# MersenneTwister.net
KiCad netlist of a schematic drawn in EAGLE
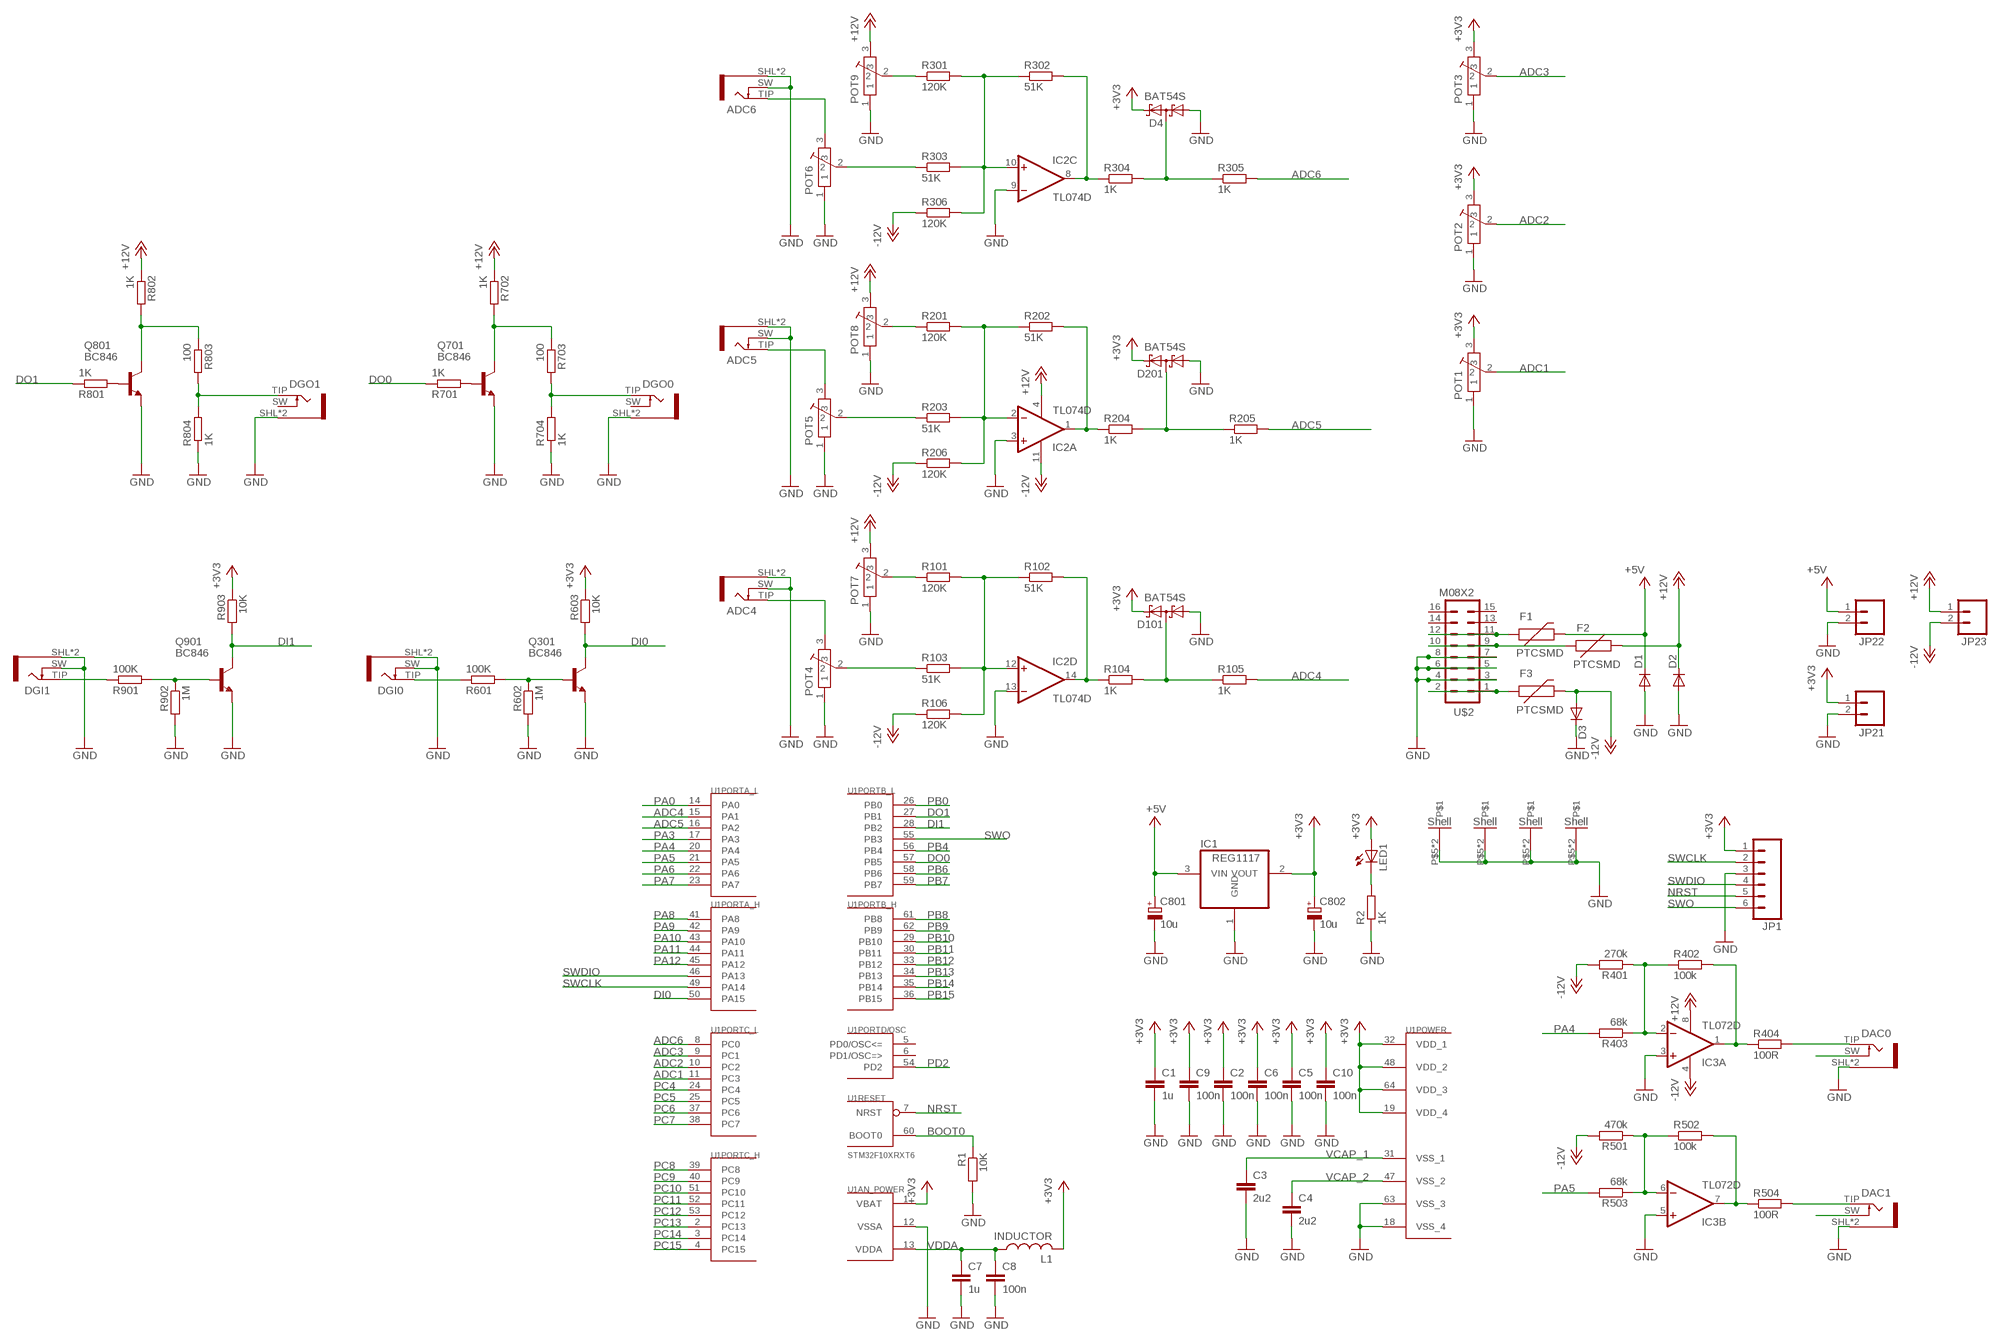
[diagram p0: schematic, sheet 1]

(export (version "E")
  (design (tool "Eeschema 10.0.6"))
  (components
    (comp (ref "ADC4")
      (value "JACK-PJ-301B")
      (footprint "eagle-import:PJ-301B")
      (libsource (lib "eagle-import") (part "JACK-PJ-301B"))
    )
    (comp (ref "ADC5")
      (value "JACK-PJ-301B")
      (footprint "eagle-import:PJ-301B")
      (libsource (lib "eagle-import") (part "JACK-PJ-301B"))
    )
    (comp (ref "ADC6")
      (value "JACK-PJ-301B")
      (footprint "eagle-import:PJ-301B")
      (libsource (lib "eagle-import") (part "JACK-PJ-301B"))
    )
    (comp (ref "C1")
      (value "1u")
      (footprint "eagle-import:C0603")
      (libsource (lib "eagle-import") (part "C-EUC0603"))
    )
    (comp (ref "C2")
      (value "100n")
      (footprint "eagle-import:C0603")
      (libsource (lib "eagle-import") (part "C-EUC0603"))
    )
    (comp (ref "C3")
      (value "2u2")
      (footprint "eagle-import:C0603")
      (libsource (lib "eagle-import") (part "C-EUC0603"))
    )
    (comp (ref "C4")
      (value "2u2")
      (footprint "eagle-import:C0603")
      (libsource (lib "eagle-import") (part "C-EUC0603"))
    )
    (comp (ref "C5")
      (value "100n")
      (footprint "eagle-import:C0603")
      (libsource (lib "eagle-import") (part "C-EUC0603"))
    )
    (comp (ref "C6")
      (value "100n")
      (footprint "eagle-import:C0603")
      (libsource (lib "eagle-import") (part "C-EUC0603"))
    )
    (comp (ref "C7")
      (value "1u")
      (footprint "eagle-import:C0603")
      (libsource (lib "eagle-import") (part "C-EUC0603"))
    )
    (comp (ref "C8")
      (value "100n")
      (footprint "eagle-import:C0603")
      (libsource (lib "eagle-import") (part "C-EUC0603"))
    )
    (comp (ref "C9")
      (value "100n")
      (footprint "eagle-import:C0603")
      (libsource (lib "eagle-import") (part "C-EUC0603"))
    )
    (comp (ref "C10")
      (value "100n")
      (footprint "eagle-import:C0603")
      (libsource (lib "eagle-import") (part "C-EUC0603"))
    )
    (comp (ref "C801")
      (value "10u")
      (footprint "eagle-import:PANASONIC_A")
      (libsource (lib "eagle-import") (part "CPOL-EUA"))
    )
    (comp (ref "C802")
      (value "10u")
      (footprint "eagle-import:PANASONIC_A")
      (libsource (lib "eagle-import") (part "CPOL-EUA"))
    )
    (comp (ref "D1")
      (value "DIODESMA")
      (footprint "eagle-import:SMA-DIODE")
      (libsource (lib "eagle-import") (part "DIODESMA"))
    )
    (comp (ref "D2")
      (value "DIODESMA")
      (footprint "eagle-import:SMA-DIODE")
      (libsource (lib "eagle-import") (part "DIODESMA"))
    )
    (comp (ref "D3")
      (value "DIODESMA")
      (footprint "eagle-import:SMA-DIODE")
      (libsource (lib "eagle-import") (part "DIODESMA"))
    )
    (comp (ref "D4")
      (value "BAT54S")
      (footprint "eagle-import:SOT23")
      (libsource (lib "eagle-import") (part "BAT54S"))
    )
    (comp (ref "D101")
      (value "BAT54S")
      (footprint "eagle-import:SOT23")
      (libsource (lib "eagle-import") (part "BAT54S"))
    )
    (comp (ref "D201")
      (value "BAT54S")
      (footprint "eagle-import:SOT23")
      (libsource (lib "eagle-import") (part "BAT54S"))
    )
    (comp (ref "DAC0")
      (value "JACK-PJ-301B")
      (footprint "eagle-import:PJ-301B")
      (libsource (lib "eagle-import") (part "JACK-PJ-301B"))
    )
    (comp (ref "DAC1")
      (value "JACK-PJ-301B")
      (footprint "eagle-import:PJ-301B")
      (libsource (lib "eagle-import") (part "JACK-PJ-301B"))
    )
    (comp (ref "DGI0")
      (value "JACK-PJ-301B")
      (footprint "eagle-import:PJ-301B")
      (libsource (lib "eagle-import") (part "JACK-PJ-301B"))
    )
    (comp (ref "DGI1")
      (value "JACK-PJ-301B")
      (footprint "eagle-import:PJ-301B")
      (libsource (lib "eagle-import") (part "JACK-PJ-301B"))
    )
    (comp (ref "DGO0")
      (value "JACK-PJ-301B")
      (footprint "eagle-import:PJ-301B")
      (libsource (lib "eagle-import") (part "JACK-PJ-301B"))
    )
    (comp (ref "DGO1")
      (value "JACK-PJ-301B")
      (footprint "eagle-import:PJ-301B")
      (libsource (lib "eagle-import") (part "JACK-PJ-301B"))
    )
    (comp (ref "F1")
      (value "PTCSMD")
      (footprint "eagle-import:PTC-1206")
      (libsource (lib "eagle-import") (part "PTCSMD"))
    )
    (comp (ref "F2")
      (value "PTCSMD")
      (footprint "eagle-import:PTC-1206")
      (libsource (lib "eagle-import") (part "PTCSMD"))
    )
    (comp (ref "F3")
      (value "PTCSMD")
      (footprint "eagle-import:PTC-1206")
      (libsource (lib "eagle-import") (part "PTCSMD"))
    )
    (comp (ref "IC1")
      (value "REG1117")
      (footprint "eagle-import:SOT223")
      (libsource (lib "eagle-import") (part "REG1117"))
    )
    (comp (ref "IC2")
      (value "TL074D")
      (footprint "eagle-import:SO14")
      (libsource (lib "eagle-import") (part "TL074D"))
    )
    (comp (ref "IC3")
      (value "TL072D")
      (footprint "eagle-import:SO08")
      (libsource (lib "eagle-import") (part "TL072D"))
    )
    (comp (ref "JP1")
      (value "M06SIP")
      (footprint "eagle-import:1X06")
      (libsource (lib "eagle-import") (part "M06SIP"))
    )
    (comp (ref "JP21")
      (value "M02PTH")
      (footprint "eagle-import:1X02")
      (libsource (lib "eagle-import") (part "M02PTH"))
    )
    (comp (ref "JP22")
      (value "M02PTH")
      (footprint "eagle-import:1X02")
      (libsource (lib "eagle-import") (part "M02PTH"))
    )
    (comp (ref "JP23")
      (value "M02PTH")
      (footprint "eagle-import:1X02")
      (libsource (lib "eagle-import") (part "M02PTH"))
    )
    (comp (ref "L1")
      (value "INDUCTOR")
      (footprint "eagle-import:0603")
      (libsource (lib "eagle-import") (part "INDUCTOR"))
    )
    (comp (ref "LED1")
      (value "LEDCHIPLED_0603")
      (footprint "eagle-import:CHIPLED_0603")
      (libsource (lib "eagle-import") (part "LEDCHIPLED_0603"))
    )
    (comp (ref "POT1")
      (value "POT-ALPS-RK09L1140")
      (footprint "eagle-import:POT-ALPS-RK09L1140")
      (libsource (lib "eagle-import") (part "POT-ALPS-RK09L1140"))
    )
    (comp (ref "POT2")
      (value "POT-ALPS-RK09L1140")
      (footprint "eagle-import:POT-ALPS-RK09L1140")
      (libsource (lib "eagle-import") (part "POT-ALPS-RK09L1140"))
    )
    (comp (ref "POT3")
      (value "POT-ALPS-RK09L1140")
      (footprint "eagle-import:POT-ALPS-RK09L1140")
      (libsource (lib "eagle-import") (part "POT-ALPS-RK09L1140"))
    )
    (comp (ref "POT4")
      (value "POT-ALPS-RK09L1140")
      (footprint "eagle-import:POT-ALPS-RK09L1140")
      (libsource (lib "eagle-import") (part "POT-ALPS-RK09L1140"))
    )
    (comp (ref "POT5")
      (value "POT-ALPS-RK09L1140")
      (footprint "eagle-import:POT-ALPS-RK09L1140")
      (libsource (lib "eagle-import") (part "POT-ALPS-RK09L1140"))
    )
    (comp (ref "POT6")
      (value "POT-ALPS-RK09L1140")
      (footprint "eagle-import:POT-ALPS-RK09L1140")
      (libsource (lib "eagle-import") (part "POT-ALPS-RK09L1140"))
    )
    (comp (ref "POT7")
      (value "POT-ALPS-RK09L1140")
      (footprint "eagle-import:POT-ALPS-RK09L1140")
      (libsource (lib "eagle-import") (part "POT-ALPS-RK09L1140"))
    )
    (comp (ref "POT8")
      (value "POT-ALPS-RK09L1140")
      (footprint "eagle-import:POT-ALPS-RK09L1140")
      (libsource (lib "eagle-import") (part "POT-ALPS-RK09L1140"))
    )
    (comp (ref "POT9")
      (value "POT-ALPS-RK09L1140")
      (footprint "eagle-import:POT-ALPS-RK09L1140")
      (libsource (lib "eagle-import") (part "POT-ALPS-RK09L1140"))
    )
    (comp (ref "Q301")
      (value "BC846")
      (footprint "eagle-import:SOT23")
      (libsource (lib "eagle-import") (part "BC846"))
    )
    (comp (ref "Q701")
      (value "BC846")
      (footprint "eagle-import:SOT23")
      (libsource (lib "eagle-import") (part "BC846"))
    )
    (comp (ref "Q801")
      (value "BC846")
      (footprint "eagle-import:SOT23")
      (libsource (lib "eagle-import") (part "BC846"))
    )
    (comp (ref "Q901")
      (value "BC846")
      (footprint "eagle-import:SOT23")
      (libsource (lib "eagle-import") (part "BC846"))
    )
    (comp (ref "R1")
      (value "10K")
      (footprint "eagle-import:R0603")
      (libsource (lib "eagle-import") (part "R-EU_R0603"))
    )
    (comp (ref "R2")
      (value "1K")
      (footprint "eagle-import:R0603")
      (libsource (lib "eagle-import") (part "R-EU_R0603"))
    )
    (comp (ref "R101")
      (value "120K")
      (footprint "eagle-import:R0603")
      (libsource (lib "eagle-import") (part "R-EU_R0603"))
    )
    (comp (ref "R102")
      (value "51K")
      (footprint "eagle-import:R0603")
      (libsource (lib "eagle-import") (part "R-EU_R0603"))
    )
    (comp (ref "R103")
      (value "51K")
      (footprint "eagle-import:R0603")
      (libsource (lib "eagle-import") (part "R-EU_R0603"))
    )
    (comp (ref "R104")
      (value "1K")
      (footprint "eagle-import:R0603")
      (libsource (lib "eagle-import") (part "R-EU_R0603"))
    )
    (comp (ref "R105")
      (value "1K")
      (footprint "eagle-import:R0603")
      (libsource (lib "eagle-import") (part "R-EU_R0603"))
    )
    (comp (ref "R106")
      (value "120K")
      (footprint "eagle-import:R0603")
      (libsource (lib "eagle-import") (part "R-EU_R0603"))
    )
    (comp (ref "R201")
      (value "120K")
      (footprint "eagle-import:R0603")
      (libsource (lib "eagle-import") (part "R-EU_R0603"))
    )
    (comp (ref "R202")
      (value "51K")
      (footprint "eagle-import:R0603")
      (libsource (lib "eagle-import") (part "R-EU_R0603"))
    )
    (comp (ref "R203")
      (value "51K")
      (footprint "eagle-import:R0603")
      (libsource (lib "eagle-import") (part "R-EU_R0603"))
    )
    (comp (ref "R204")
      (value "1K")
      (footprint "eagle-import:R0603")
      (libsource (lib "eagle-import") (part "R-EU_R0603"))
    )
    (comp (ref "R205")
      (value "1K")
      (footprint "eagle-import:R0603")
      (libsource (lib "eagle-import") (part "R-EU_R0603"))
    )
    (comp (ref "R206")
      (value "120K")
      (footprint "eagle-import:R0603")
      (libsource (lib "eagle-import") (part "R-EU_R0603"))
    )
    (comp (ref "R301")
      (value "120K")
      (footprint "eagle-import:R0603")
      (libsource (lib "eagle-import") (part "R-EU_R0603"))
    )
    (comp (ref "R302")
      (value "51K")
      (footprint "eagle-import:R0603")
      (libsource (lib "eagle-import") (part "R-EU_R0603"))
    )
    (comp (ref "R303")
      (value "51K")
      (footprint "eagle-import:R0603")
      (libsource (lib "eagle-import") (part "R-EU_R0603"))
    )
    (comp (ref "R304")
      (value "1K")
      (footprint "eagle-import:R0603")
      (libsource (lib "eagle-import") (part "R-EU_R0603"))
    )
    (comp (ref "R305")
      (value "1K")
      (footprint "eagle-import:R0603")
      (libsource (lib "eagle-import") (part "R-EU_R0603"))
    )
    (comp (ref "R306")
      (value "120K")
      (footprint "eagle-import:R0603")
      (libsource (lib "eagle-import") (part "R-EU_R0603"))
    )
    (comp (ref "R401")
      (value "270k")
      (footprint "eagle-import:R0603")
      (libsource (lib "eagle-import") (part "R-EU_R0603"))
    )
    (comp (ref "R402")
      (value "100k")
      (footprint "eagle-import:R0603")
      (libsource (lib "eagle-import") (part "R-EU_R0603"))
    )
    (comp (ref "R403")
      (value "68k")
      (footprint "eagle-import:R0603")
      (libsource (lib "eagle-import") (part "R-EU_R0603"))
    )
    (comp (ref "R404")
      (value "100R")
      (footprint "eagle-import:R0603")
      (libsource (lib "eagle-import") (part "R-EU_R0603"))
    )
    (comp (ref "R501")
      (value "470k")
      (footprint "eagle-import:R0603")
      (libsource (lib "eagle-import") (part "R-EU_R0603"))
    )
    (comp (ref "R502")
      (value "100k")
      (footprint "eagle-import:R0603")
      (libsource (lib "eagle-import") (part "R-EU_R0603"))
    )
    (comp (ref "R503")
      (value "68k")
      (footprint "eagle-import:R0603")
      (libsource (lib "eagle-import") (part "R-EU_R0603"))
    )
    (comp (ref "R504")
      (value "100R")
      (footprint "eagle-import:R0603")
      (libsource (lib "eagle-import") (part "R-EU_R0603"))
    )
    (comp (ref "R601")
      (value "100K")
      (footprint "eagle-import:R0603")
      (libsource (lib "eagle-import") (part "R-EU_R0603"))
    )
    (comp (ref "R602")
      (value "1M")
      (footprint "eagle-import:R0603")
      (libsource (lib "eagle-import") (part "R-EU_R0603"))
    )
    (comp (ref "R603")
      (value "10K")
      (footprint "eagle-import:R0603")
      (libsource (lib "eagle-import") (part "R-EU_R0603"))
    )
    (comp (ref "R701")
      (value "1K")
      (footprint "eagle-import:R0603")
      (libsource (lib "eagle-import") (part "R-EU_R0603"))
    )
    (comp (ref "R702")
      (value "1K")
      (footprint "eagle-import:R0603")
      (libsource (lib "eagle-import") (part "R-EU_R0603"))
    )
    (comp (ref "R703")
      (value "100")
      (footprint "eagle-import:R0603")
      (libsource (lib "eagle-import") (part "R-EU_R0603"))
    )
    (comp (ref "R704")
      (value "1K")
      (footprint "eagle-import:R0603")
      (libsource (lib "eagle-import") (part "R-EU_R0603"))
    )
    (comp (ref "R801")
      (value "1K")
      (footprint "eagle-import:R0603")
      (libsource (lib "eagle-import") (part "R-EU_R0603"))
    )
    (comp (ref "R802")
      (value "1K")
      (footprint "eagle-import:R0603")
      (libsource (lib "eagle-import") (part "R-EU_R0603"))
    )
    (comp (ref "R803")
      (value "100")
      (footprint "eagle-import:R0603")
      (libsource (lib "eagle-import") (part "R-EU_R0603"))
    )
    (comp (ref "R804")
      (value "1K")
      (footprint "eagle-import:R0603")
      (libsource (lib "eagle-import") (part "R-EU_R0603"))
    )
    (comp (ref "R901")
      (value "100K")
      (footprint "eagle-import:R0603")
      (libsource (lib "eagle-import") (part "R-EU_R0603"))
    )
    (comp (ref "R902")
      (value "1M")
      (footprint "eagle-import:R0603")
      (libsource (lib "eagle-import") (part "R-EU_R0603"))
    )
    (comp (ref "R903")
      (value "10K")
      (footprint "eagle-import:R0603")
      (libsource (lib "eagle-import") (part "R-EU_R0603"))
    )
    (comp (ref "U$2")
      (value "M08X2")
      (footprint "eagle-import:2X8")
      (libsource (lib "eagle-import") (part "M08X2"))
    )
    (comp (ref "U1")
      (value "STM32F10XRXT6")
      (footprint "eagle-import:TQFP64")
      (libsource (lib "eagle-import") (part "STM32F10XRXT6"))
    )
  )
  (nets
    (net (code "1") (name "+3V3") (class "Default")
      (node (ref "C1") (pin "1") (pinfunction "1_1") (pintype "passive"))
      (node (ref "C10") (pin "1") (pinfunction "1_1") (pintype "passive"))
      (node (ref "C2") (pin "1") (pinfunction "1_1") (pintype "passive"))
      (node (ref "C5") (pin "1") (pinfunction "1_1") (pintype "passive"))
      (node (ref "C6") (pin "1") (pinfunction "1_1") (pintype "passive"))
      (node (ref "C802") (pin "+") (pinfunction "+_+") (pintype "passive"))
      (node (ref "C9") (pin "1") (pinfunction "1_1") (pintype "passive"))
      (node (ref "D101") (pin "2") (pinfunction "C2_2") (pintype "passive"))
      (node (ref "D201") (pin "2") (pinfunction "C2_2") (pintype "passive"))
      (node (ref "D4") (pin "2") (pinfunction "C2_2") (pintype "passive"))
      (node (ref "IC1") (pin "2") (pinfunction "VOUT_2") (pintype "output"))
      (node (ref "JP1") (pin "1") (pinfunction "1_1") (pintype "passive"))
      (node (ref "JP21") (pin "1") (pinfunction "1_1") (pintype "passive"))
      (node (ref "L1") (pin "2") (pinfunction "2_2") (pintype "passive"))
      (node (ref "LED1") (pin "A") (pinfunction "A_A") (pintype "passive"))
      (node (ref "POT1") (pin "3") (pinfunction "3_3") (pintype "bidirectional"))
      (node (ref "POT2") (pin "3") (pinfunction "3_3") (pintype "bidirectional"))
      (node (ref "POT3") (pin "3") (pinfunction "3_3") (pintype "bidirectional"))
      (node (ref "R603") (pin "1") (pinfunction "1_1") (pintype "passive"))
      (node (ref "R903") (pin "1") (pinfunction "1_1") (pintype "passive"))
      (node (ref "U1") (pin "1") (pinfunction "VBAT_1") (pintype "power_in"))
      (node (ref "U1") (pin "19") (pinfunction "VDD_4_19") (pintype "power_in"))
      (node (ref "U1") (pin "32") (pinfunction "VDD_1_32") (pintype "power_in"))
      (node (ref "U1") (pin "48") (pinfunction "VDD_2_48") (pintype "power_in"))
      (node (ref "U1") (pin "64") (pinfunction "VDD_3_64") (pintype "power_in"))
    )
    (net (code "2") (name "+5V") (class "Default")
      (node (ref "C801") (pin "+") (pinfunction "+_+") (pintype "passive"))
      (node (ref "D1") (pin "C") (pinfunction "C_C") (pintype "passive"))
      (node (ref "F1") (pin "2") (pinfunction "2_2") (pintype "bidirectional"))
      (node (ref "IC1") (pin "3") (pinfunction "VIN_3") (pintype "input"))
      (node (ref "JP22") (pin "1") (pinfunction "1_1") (pintype "passive"))
    )
    (net (code "3") (name "+12V") (class "Default")
      (node (ref "D2") (pin "C") (pinfunction "C_C") (pintype "passive"))
      (node (ref "F2") (pin "2") (pinfunction "2_2") (pintype "bidirectional"))
      (node (ref "IC2") (pin "4") (pinfunction "V+_4") (pintype "power_in"))
      (node (ref "IC3") (pin "8") (pinfunction "V+_8") (pintype "power_in"))
      (node (ref "JP23") (pin "1") (pinfunction "1_1") (pintype "passive"))
      (node (ref "POT7") (pin "3") (pinfunction "3_3") (pintype "bidirectional"))
      (node (ref "POT8") (pin "3") (pinfunction "3_3") (pintype "bidirectional"))
      (node (ref "POT9") (pin "3") (pinfunction "3_3") (pintype "bidirectional"))
      (node (ref "R702") (pin "1") (pinfunction "1_1") (pintype "passive"))
      (node (ref "R802") (pin "1") (pinfunction "1_1") (pintype "passive"))
    )
    (net (code "4") (name "-12V") (class "Default")
      (node (ref "D3") (pin "A") (pinfunction "A_A") (pintype "passive"))
      (node (ref "F3") (pin "2") (pinfunction "2_2") (pintype "bidirectional"))
      (node (ref "IC2") (pin "11") (pinfunction "V-_11") (pintype "power_in"))
      (node (ref "IC3") (pin "4") (pinfunction "V-_4") (pintype "power_in"))
      (node (ref "JP23") (pin "2") (pinfunction "2_2") (pintype "passive"))
      (node (ref "R106") (pin "1") (pinfunction "1_1") (pintype "passive"))
      (node (ref "R206") (pin "1") (pinfunction "1_1") (pintype "passive"))
      (node (ref "R306") (pin "1") (pinfunction "1_1") (pintype "passive"))
      (node (ref "R401") (pin "2") (pinfunction "2_2") (pintype "passive"))
      (node (ref "R501") (pin "2") (pinfunction "2_2") (pintype "passive"))
    )
    (net (code "5") (name "/ADC1") (class "Default")
      (node (ref "POT1") (pin "2") (pinfunction "2_2") (pintype "bidirectional"))
      (node (ref "U1") (pin "11") (pinfunction "PC3_11") (pintype "bidirectional"))
    )
    (net (code "6") (name "/ADC2") (class "Default")
      (node (ref "POT2") (pin "2") (pinfunction "2_2") (pintype "bidirectional"))
      (node (ref "U1") (pin "10") (pinfunction "PC2_10") (pintype "bidirectional"))
    )
    (net (code "7") (name "/ADC3") (class "Default")
      (node (ref "POT3") (pin "2") (pinfunction "2_2") (pintype "bidirectional"))
      (node (ref "U1") (pin "9") (pinfunction "PC1_9") (pintype "bidirectional"))
    )
    (net (code "8") (name "/ADC4") (class "Default")
      (node (ref "R105") (pin "2") (pinfunction "2_2") (pintype "passive"))
      (node (ref "U1") (pin "15") (pinfunction "PA1_15") (pintype "bidirectional"))
    )
    (net (code "9") (name "/ADC5") (class "Default")
      (node (ref "R205") (pin "2") (pinfunction "2_2") (pintype "passive"))
      (node (ref "U1") (pin "16") (pinfunction "PA2_16") (pintype "bidirectional"))
    )
    (net (code "10") (name "/ADC6") (class "Default")
      (node (ref "R305") (pin "2") (pinfunction "2_2") (pintype "passive"))
      (node (ref "U1") (pin "8") (pinfunction "PC0_8") (pintype "bidirectional"))
    )
    (net (code "11") (name "/BOOT0") (class "Default")
      (node (ref "R1") (pin "1") (pinfunction "1_1") (pintype "passive"))
      (node (ref "U1") (pin "60") (pinfunction "BOOT0_60") (pintype "input"))
    )
    (net (code "12") (name "/DI0") (class "Default")
      (node (ref "Q301") (pin "3") (pinfunction "C_3") (pintype "passive"))
      (node (ref "R603") (pin "2") (pinfunction "2_2") (pintype "passive"))
      (node (ref "U1") (pin "50") (pinfunction "PA15_50") (pintype "bidirectional"))
    )
    (net (code "13") (name "/DI1") (class "Default")
      (node (ref "Q901") (pin "3") (pinfunction "C_3") (pintype "passive"))
      (node (ref "R903") (pin "2") (pinfunction "2_2") (pintype "passive"))
      (node (ref "U1") (pin "28") (pinfunction "PB2_28") (pintype "bidirectional"))
    )
    (net (code "14") (name "/DO0") (class "Default")
      (node (ref "R701") (pin "1") (pinfunction "1_1") (pintype "passive"))
      (node (ref "U1") (pin "57") (pinfunction "PB5_57") (pintype "bidirectional"))
    )
    (net (code "15") (name "/DO1") (class "Default")
      (node (ref "R801") (pin "1") (pinfunction "1_1") (pintype "passive"))
      (node (ref "U1") (pin "27") (pinfunction "PB1_27") (pintype "bidirectional"))
    )
    (net (code "16") (name "/NRST") (class "Default")
      (node (ref "JP1") (pin "5") (pinfunction "5_5") (pintype "passive"))
      (node (ref "U1") (pin "7") (pinfunction "NRST_7") (pintype "input"))
    )
    (net (code "17") (name "/PA0") (class "Default")
      (node (ref "U1") (pin "14") (pinfunction "PA0_14") (pintype "bidirectional"))
    )
    (net (code "18") (name "/PA3") (class "Default")
      (node (ref "U1") (pin "17") (pinfunction "PA3_17") (pintype "bidirectional"))
    )
    (net (code "19") (name "/PA4") (class "Default")
      (node (ref "R403") (pin "2") (pinfunction "2_2") (pintype "passive"))
      (node (ref "U1") (pin "20") (pinfunction "PA4_20") (pintype "bidirectional"))
    )
    (net (code "20") (name "/PA5") (class "Default")
      (node (ref "R503") (pin "2") (pinfunction "2_2") (pintype "passive"))
      (node (ref "U1") (pin "21") (pinfunction "PA5_21") (pintype "bidirectional"))
    )
    (net (code "21") (name "/PA6") (class "Default")
      (node (ref "U1") (pin "22") (pinfunction "PA6_22") (pintype "bidirectional"))
    )
    (net (code "22") (name "/PA7") (class "Default")
      (node (ref "U1") (pin "23") (pinfunction "PA7_23") (pintype "bidirectional"))
    )
    (net (code "23") (name "/PA8") (class "Default")
      (node (ref "U1") (pin "41") (pinfunction "PA8_41") (pintype "bidirectional"))
    )
    (net (code "24") (name "/PA9") (class "Default")
      (node (ref "U1") (pin "42") (pinfunction "PA9_42") (pintype "bidirectional"))
    )
    (net (code "25") (name "/PA10") (class "Default")
      (node (ref "U1") (pin "43") (pinfunction "PA10_43") (pintype "bidirectional"))
    )
    (net (code "26") (name "/PA11") (class "Default")
      (node (ref "U1") (pin "44") (pinfunction "PA11_44") (pintype "bidirectional"))
    )
    (net (code "27") (name "/PA12") (class "Default")
      (node (ref "U1") (pin "45") (pinfunction "PA12_45") (pintype "bidirectional"))
    )
    (net (code "28") (name "/PB0") (class "Default")
      (node (ref "U1") (pin "26") (pinfunction "PB0_26") (pintype "bidirectional"))
    )
    (net (code "29") (name "/PB4") (class "Default")
      (node (ref "U1") (pin "56") (pinfunction "PB4_56") (pintype "bidirectional"))
    )
    (net (code "30") (name "/PB6") (class "Default")
      (node (ref "U1") (pin "58") (pinfunction "PB6_58") (pintype "bidirectional"))
    )
    (net (code "31") (name "/PB7") (class "Default")
      (node (ref "U1") (pin "59") (pinfunction "PB7_59") (pintype "bidirectional"))
    )
    (net (code "32") (name "/PB8") (class "Default")
      (node (ref "U1") (pin "61") (pinfunction "PB8_61") (pintype "bidirectional"))
    )
    (net (code "33") (name "/PB9") (class "Default")
      (node (ref "U1") (pin "62") (pinfunction "PB9_62") (pintype "bidirectional"))
    )
    (net (code "34") (name "/PB10") (class "Default")
      (node (ref "U1") (pin "29") (pinfunction "PB10_29") (pintype "bidirectional"))
    )
    (net (code "35") (name "/PB11") (class "Default")
      (node (ref "U1") (pin "30") (pinfunction "PB11_30") (pintype "bidirectional"))
    )
    (net (code "36") (name "/PB12") (class "Default")
      (node (ref "U1") (pin "33") (pinfunction "PB12_33") (pintype "bidirectional"))
    )
    (net (code "37") (name "/PB13") (class "Default")
      (node (ref "U1") (pin "34") (pinfunction "PB13_34") (pintype "bidirectional"))
    )
    (net (code "38") (name "/PB14") (class "Default")
      (node (ref "U1") (pin "35") (pinfunction "PB14_35") (pintype "bidirectional"))
    )
    (net (code "39") (name "/PB15") (class "Default")
      (node (ref "U1") (pin "36") (pinfunction "PB15_36") (pintype "bidirectional"))
    )
    (net (code "40") (name "/PC4") (class "Default")
      (node (ref "U1") (pin "24") (pinfunction "PC4_24") (pintype "bidirectional"))
    )
    (net (code "41") (name "/PC5") (class "Default")
      (node (ref "U1") (pin "25") (pinfunction "PC5_25") (pintype "bidirectional"))
    )
    (net (code "42") (name "/PC6") (class "Default")
      (node (ref "U1") (pin "37") (pinfunction "PC6_37") (pintype "bidirectional"))
    )
    (net (code "43") (name "/PC7") (class "Default")
      (node (ref "U1") (pin "38") (pinfunction "PC7_38") (pintype "bidirectional"))
    )
    (net (code "44") (name "/PC8") (class "Default")
      (node (ref "U1") (pin "39") (pinfunction "PC8_39") (pintype "bidirectional"))
    )
    (net (code "45") (name "/PC9") (class "Default")
      (node (ref "U1") (pin "40") (pinfunction "PC9_40") (pintype "bidirectional"))
    )
    (net (code "46") (name "/PC10") (class "Default")
      (node (ref "U1") (pin "51") (pinfunction "PC10_51") (pintype "bidirectional"))
    )
    (net (code "47") (name "/PC11") (class "Default")
      (node (ref "U1") (pin "52") (pinfunction "PC11_52") (pintype "bidirectional"))
    )
    (net (code "48") (name "/PC12") (class "Default")
      (node (ref "U1") (pin "53") (pinfunction "PC12_53") (pintype "bidirectional"))
    )
    (net (code "49") (name "/PC13") (class "Default")
      (node (ref "U1") (pin "2") (pinfunction "PC13_2") (pintype "bidirectional"))
    )
    (net (code "50") (name "/PC14") (class "Default")
      (node (ref "U1") (pin "3") (pinfunction "PC14_3") (pintype "bidirectional"))
    )
    (net (code "51") (name "/PC15") (class "Default")
      (node (ref "U1") (pin "4") (pinfunction "PC15_4") (pintype "bidirectional"))
    )
    (net (code "52") (name "/PD2") (class "Default")
      (node (ref "U1") (pin "54") (pinfunction "PD2_54") (pintype "bidirectional"))
    )
    (net (code "53") (name "/SWCLK") (class "Default")
      (node (ref "JP1") (pin "2") (pinfunction "2_2") (pintype "passive"))
      (node (ref "U1") (pin "49") (pinfunction "PA14_49") (pintype "bidirectional"))
    )
    (net (code "54") (name "/SWDIO") (class "Default")
      (node (ref "JP1") (pin "4") (pinfunction "4_4") (pintype "passive"))
      (node (ref "U1") (pin "46") (pinfunction "PA13_46") (pintype "bidirectional"))
    )
    (net (code "55") (name "/SWO") (class "Default")
      (node (ref "JP1") (pin "6") (pinfunction "6_6") (pintype "passive"))
      (node (ref "U1") (pin "55") (pinfunction "PB3_55") (pintype "bidirectional"))
    )
    (net (code "56") (name "/VCAP_1") (class "Default")
      (node (ref "C3") (pin "1") (pinfunction "1_1") (pintype "passive"))
      (node (ref "U1") (pin "31") (pinfunction "VSS_1_31") (pintype "power_in"))
    )
    (net (code "57") (name "/VCAP_2") (class "Default")
      (node (ref "C4") (pin "1") (pinfunction "1_1") (pintype "passive"))
      (node (ref "U1") (pin "47") (pinfunction "VSS_2_47") (pintype "power_in"))
    )
    (net (code "58") (name "/VDDA") (class "Default")
      (node (ref "C7") (pin "1") (pinfunction "1_1") (pintype "passive"))
      (node (ref "C8") (pin "1") (pinfunction "1_1") (pintype "passive"))
      (node (ref "L1") (pin "1") (pinfunction "1_1") (pintype "passive"))
      (node (ref "U1") (pin "13") (pinfunction "VDDA_13") (pintype "power_in"))
    )
    (net (code "59") (name "GND") (class "Default")
      (node (ref "ADC4") (pin "SHL") (pinfunction "SLEEVE_SHL") (pintype "passive"))
      (node (ref "ADC4") (pin "SLV") (pinfunction "SLEEVE_SLV") (pintype "passive"))
      (node (ref "ADC4") (pin "SW") (pinfunction "SW_SW") (pintype "passive"))
      (node (ref "ADC5") (pin "SHL") (pinfunction "SLEEVE_SHL") (pintype "passive"))
      (node (ref "ADC5") (pin "SLV") (pinfunction "SLEEVE_SLV") (pintype "passive"))
      (node (ref "ADC5") (pin "SW") (pinfunction "SW_SW") (pintype "passive"))
      (node (ref "ADC6") (pin "SHL") (pinfunction "SLEEVE_SHL") (pintype "passive"))
      (node (ref "ADC6") (pin "SLV") (pinfunction "SLEEVE_SLV") (pintype "passive"))
      (node (ref "ADC6") (pin "SW") (pinfunction "SW_SW") (pintype "passive"))
      (node (ref "C1") (pin "2") (pinfunction "2_2") (pintype "passive"))
      (node (ref "C10") (pin "2") (pinfunction "2_2") (pintype "passive"))
      (node (ref "C2") (pin "2") (pinfunction "2_2") (pintype "passive"))
      (node (ref "C3") (pin "2") (pinfunction "2_2") (pintype "passive"))
      (node (ref "C4") (pin "2") (pinfunction "2_2") (pintype "passive"))
      (node (ref "C5") (pin "2") (pinfunction "2_2") (pintype "passive"))
      (node (ref "C6") (pin "2") (pinfunction "2_2") (pintype "passive"))
      (node (ref "C7") (pin "2") (pinfunction "2_2") (pintype "passive"))
      (node (ref "C8") (pin "2") (pinfunction "2_2") (pintype "passive"))
      (node (ref "C801") (pin "-") (pinfunction "-_-") (pintype "passive"))
      (node (ref "C802") (pin "-") (pinfunction "-_-") (pintype "passive"))
      (node (ref "C9") (pin "2") (pinfunction "2_2") (pintype "passive"))
      (node (ref "D1") (pin "A") (pinfunction "A_A") (pintype "passive"))
      (node (ref "D101") (pin "1") (pinfunction "A1_1") (pintype "passive"))
      (node (ref "D2") (pin "A") (pinfunction "A_A") (pintype "passive"))
      (node (ref "D201") (pin "1") (pinfunction "A1_1") (pintype "passive"))
      (node (ref "D3") (pin "C") (pinfunction "C_C") (pintype "passive"))
      (node (ref "D4") (pin "1") (pinfunction "A1_1") (pintype "passive"))
      (node (ref "DAC0") (pin "SHL") (pinfunction "SLEEVE_SHL") (pintype "passive"))
      (node (ref "DAC0") (pin "SLV") (pinfunction "SLEEVE_SLV") (pintype "passive"))
      (node (ref "DAC1") (pin "SHL") (pinfunction "SLEEVE_SHL") (pintype "passive"))
      (node (ref "DAC1") (pin "SLV") (pinfunction "SLEEVE_SLV") (pintype "passive"))
      (node (ref "DGI0") (pin "SHL") (pinfunction "SLEEVE_SHL") (pintype "passive"))
      (node (ref "DGI0") (pin "SLV") (pinfunction "SLEEVE_SLV") (pintype "passive"))
      (node (ref "DGI0") (pin "SW") (pinfunction "SW_SW") (pintype "passive"))
      (node (ref "DGI1") (pin "SHL") (pinfunction "SLEEVE_SHL") (pintype "passive"))
      (node (ref "DGI1") (pin "SLV") (pinfunction "SLEEVE_SLV") (pintype "passive"))
      (node (ref "DGI1") (pin "SW") (pinfunction "SW_SW") (pintype "passive"))
      (node (ref "DGO0") (pin "SHL") (pinfunction "SLEEVE_SHL") (pintype "passive"))
      (node (ref "DGO0") (pin "SLV") (pinfunction "SLEEVE_SLV") (pintype "passive"))
      (node (ref "DGO1") (pin "SHL") (pinfunction "SLEEVE_SHL") (pintype "passive"))
      (node (ref "DGO1") (pin "SLV") (pinfunction "SLEEVE_SLV") (pintype "passive"))
      (node (ref "IC1") (pin "1") (pinfunction "GND_1") (pintype "power_in"))
      (node (ref "IC2") (pin "13") (pinfunction "-IN_13") (pintype "input"))
      (node (ref "IC2") (pin "3") (pinfunction "+IN_3") (pintype "input"))
      (node (ref "IC2") (pin "9") (pinfunction "-IN_9") (pintype "input"))
      (node (ref "IC3") (pin "3") (pinfunction "+IN_3") (pintype "input"))
      (node (ref "IC3") (pin "5") (pinfunction "+IN_5") (pintype "input"))
      (node (ref "JP1") (pin "3") (pinfunction "3_3") (pintype "passive"))
      (node (ref "JP21") (pin "2") (pinfunction "2_2") (pintype "passive"))
      (node (ref "JP22") (pin "2") (pinfunction "2_2") (pintype "passive"))
      (node (ref "POT1") (pin "1") (pinfunction "1_1") (pintype "bidirectional"))
      (node (ref "POT1") (pin "P$5") (pinfunction "P$1_P$5") (pintype "bidirectional"))
      (node (ref "POT1") (pin "P$6") (pinfunction "P$1_P$6") (pintype "bidirectional"))
      (node (ref "POT2") (pin "1") (pinfunction "1_1") (pintype "bidirectional"))
      (node (ref "POT2") (pin "P$5") (pinfunction "P$1_P$5") (pintype "bidirectional"))
      (node (ref "POT2") (pin "P$6") (pinfunction "P$1_P$6") (pintype "bidirectional"))
      (node (ref "POT3") (pin "1") (pinfunction "1_1") (pintype "bidirectional"))
      (node (ref "POT4") (pin "1") (pinfunction "1_1") (pintype "bidirectional"))
      (node (ref "POT5") (pin "1") (pinfunction "1_1") (pintype "bidirectional"))
      (node (ref "POT6") (pin "1") (pinfunction "1_1") (pintype "bidirectional"))
      (node (ref "POT7") (pin "1") (pinfunction "1_1") (pintype "bidirectional"))
      (node (ref "POT7") (pin "P$5") (pinfunction "P$1_P$5") (pintype "bidirectional"))
      (node (ref "POT7") (pin "P$6") (pinfunction "P$1_P$6") (pintype "bidirectional"))
      (node (ref "POT8") (pin "1") (pinfunction "1_1") (pintype "bidirectional"))
      (node (ref "POT8") (pin "P$5") (pinfunction "P$1_P$5") (pintype "bidirectional"))
      (node (ref "POT8") (pin "P$6") (pinfunction "P$1_P$6") (pintype "bidirectional"))
      (node (ref "POT9") (pin "1") (pinfunction "1_1") (pintype "bidirectional"))
      (node (ref "Q301") (pin "2") (pinfunction "E_2") (pintype "passive"))
      (node (ref "Q701") (pin "2") (pinfunction "E_2") (pintype "passive"))
      (node (ref "Q801") (pin "2") (pinfunction "E_2") (pintype "passive"))
      (node (ref "Q901") (pin "2") (pinfunction "E_2") (pintype "passive"))
      (node (ref "R1") (pin "2") (pinfunction "2_2") (pintype "passive"))
      (node (ref "R2") (pin "1") (pinfunction "1_1") (pintype "passive"))
      (node (ref "R602") (pin "2") (pinfunction "2_2") (pintype "passive"))
      (node (ref "R704") (pin "1") (pinfunction "1_1") (pintype "passive"))
      (node (ref "R804") (pin "1") (pinfunction "1_1") (pintype "passive"))
      (node (ref "R902") (pin "2") (pinfunction "2_2") (pintype "passive"))
      (node (ref "U$2") (pin "3") (pinfunction "3_3") (pintype "passive"))
      (node (ref "U$2") (pin "4") (pinfunction "4_4") (pintype "passive"))
      (node (ref "U$2") (pin "5") (pinfunction "5_5") (pintype "passive"))
      (node (ref "U$2") (pin "6") (pinfunction "6_6") (pintype "passive"))
      (node (ref "U$2") (pin "7") (pinfunction "7_7") (pintype "passive"))
      (node (ref "U$2") (pin "8") (pinfunction "8_8") (pintype "passive"))
      (node (ref "U1") (pin "12") (pinfunction "VSSA_12") (pintype "power_in"))
      (node (ref "U1") (pin "18") (pinfunction "VSS_4_18") (pintype "power_in"))
      (node (ref "U1") (pin "63") (pinfunction "VSS_3_63") (pintype "power_in"))
    )
    (net (code "60") (name "Net-(ADC4-PadTIP)") (class "Default")
      (node (ref "ADC4") (pin "TIP") (pinfunction "TIP_TIP") (pintype "passive"))
      (node (ref "POT4") (pin "3") (pinfunction "3_3") (pintype "bidirectional"))
    )
    (net (code "61") (name "Net-(ADC5-PadTIP)") (class "Default")
      (node (ref "ADC5") (pin "TIP") (pinfunction "TIP_TIP") (pintype "passive"))
      (node (ref "POT5") (pin "3") (pinfunction "3_3") (pintype "bidirectional"))
    )
    (net (code "62") (name "Net-(ADC6-PadTIP)") (class "Default")
      (node (ref "ADC6") (pin "TIP") (pinfunction "TIP_TIP") (pintype "passive"))
      (node (ref "POT6") (pin "3") (pinfunction "3_3") (pintype "bidirectional"))
    )
    (net (code "63") (name "Net-(D4-C1A2)") (class "Default")
      (node (ref "D4") (pin "3") (pinfunction "C1A2_3") (pintype "passive"))
      (node (ref "R304") (pin "2") (pinfunction "2_2") (pintype "passive"))
      (node (ref "R305") (pin "1") (pinfunction "1_1") (pintype "passive"))
    )
    (net (code "64") (name "Net-(D101-C1A2)") (class "Default")
      (node (ref "D101") (pin "3") (pinfunction "C1A2_3") (pintype "passive"))
      (node (ref "R104") (pin "2") (pinfunction "2_2") (pintype "passive"))
      (node (ref "R105") (pin "1") (pinfunction "1_1") (pintype "passive"))
    )
    (net (code "65") (name "Net-(D201-C1A2)") (class "Default")
      (node (ref "D201") (pin "3") (pinfunction "C1A2_3") (pintype "passive"))
      (node (ref "R204") (pin "2") (pinfunction "2_2") (pintype "passive"))
      (node (ref "R205") (pin "1") (pinfunction "1_1") (pintype "passive"))
    )
    (net (code "66") (name "Net-(DAC0-PadTIP)") (class "Default")
      (node (ref "DAC0") (pin "TIP") (pinfunction "TIP_TIP") (pintype "passive"))
      (node (ref "R404") (pin "2") (pinfunction "2_2") (pintype "passive"))
    )
    (net (code "67") (name "Net-(DAC1-PadTIP)") (class "Default")
      (node (ref "DAC1") (pin "TIP") (pinfunction "TIP_TIP") (pintype "passive"))
      (node (ref "R504") (pin "2") (pinfunction "2_2") (pintype "passive"))
    )
    (net (code "68") (name "Net-(DGI0-PadTIP)") (class "Default")
      (node (ref "DGI0") (pin "TIP") (pinfunction "TIP_TIP") (pintype "passive"))
      (node (ref "R601") (pin "1") (pinfunction "1_1") (pintype "passive"))
    )
    (net (code "69") (name "Net-(DGI1-PadTIP)") (class "Default")
      (node (ref "DGI1") (pin "TIP") (pinfunction "TIP_TIP") (pintype "passive"))
      (node (ref "R901") (pin "1") (pinfunction "1_1") (pintype "passive"))
    )
    (net (code "70") (name "Net-(DGO0-PadTIP)") (class "Default")
      (node (ref "DGO0") (pin "TIP") (pinfunction "TIP_TIP") (pintype "passive"))
      (node (ref "R703") (pin "2") (pinfunction "2_2") (pintype "passive"))
      (node (ref "R704") (pin "2") (pinfunction "2_2") (pintype "passive"))
    )
    (net (code "71") (name "Net-(DGO1-PadTIP)") (class "Default")
      (node (ref "DGO1") (pin "TIP") (pinfunction "TIP_TIP") (pintype "passive"))
      (node (ref "R803") (pin "2") (pinfunction "2_2") (pintype "passive"))
      (node (ref "R804") (pin "2") (pinfunction "2_2") (pintype "passive"))
    )
    (net (code "72") (name "Net-(F1-Pad1)") (class "Default")
      (node (ref "F1") (pin "1") (pinfunction "1_1") (pintype "bidirectional"))
      (node (ref "U$2") (pin "11") (pinfunction "11_11") (pintype "passive"))
      (node (ref "U$2") (pin "12") (pinfunction "12_12") (pintype "passive"))
    )
    (net (code "73") (name "Net-(F2-Pad1)") (class "Default")
      (node (ref "F2") (pin "1") (pinfunction "1_1") (pintype "bidirectional"))
      (node (ref "U$2") (pin "10") (pinfunction "10_10") (pintype "passive"))
      (node (ref "U$2") (pin "9") (pinfunction "9_9") (pintype "passive"))
    )
    (net (code "74") (name "Net-(F3-Pad1)") (class "Default")
      (node (ref "F3") (pin "1") (pinfunction "1_1") (pintype "bidirectional"))
      (node (ref "U$2") (pin "1") (pinfunction "1_1") (pintype "passive"))
      (node (ref "U$2") (pin "2") (pinfunction "2_2") (pintype "passive"))
    )
    (net (code "75") (name "Net-(IC2A--IN)") (class "Default")
      (node (ref "IC2") (pin "2") (pinfunction "-IN_2") (pintype "input"))
      (node (ref "R201") (pin "2") (pinfunction "2_2") (pintype "passive"))
      (node (ref "R202") (pin "1") (pinfunction "1_1") (pintype "passive"))
      (node (ref "R203") (pin "2") (pinfunction "2_2") (pintype "passive"))
      (node (ref "R206") (pin "2") (pinfunction "2_2") (pintype "passive"))
    )
    (net (code "76") (name "Net-(IC2A-OUT)") (class "Default")
      (node (ref "IC2") (pin "1") (pinfunction "OUT_1") (pintype "output"))
      (node (ref "R202") (pin "2") (pinfunction "2_2") (pintype "passive"))
      (node (ref "R204") (pin "1") (pinfunction "1_1") (pintype "passive"))
    )
    (net (code "77") (name "Net-(IC2C-+IN)") (class "Default")
      (node (ref "IC2") (pin "10") (pinfunction "+IN_10") (pintype "input"))
      (node (ref "R301") (pin "2") (pinfunction "2_2") (pintype "passive"))
      (node (ref "R302") (pin "1") (pinfunction "1_1") (pintype "passive"))
      (node (ref "R303") (pin "2") (pinfunction "2_2") (pintype "passive"))
      (node (ref "R306") (pin "2") (pinfunction "2_2") (pintype "passive"))
    )
    (net (code "78") (name "Net-(IC2C-OUT)") (class "Default")
      (node (ref "IC2") (pin "8") (pinfunction "OUT_8") (pintype "output"))
      (node (ref "R302") (pin "2") (pinfunction "2_2") (pintype "passive"))
      (node (ref "R304") (pin "1") (pinfunction "1_1") (pintype "passive"))
    )
    (net (code "79") (name "Net-(IC2D-+IN)") (class "Default")
      (node (ref "IC2") (pin "12") (pinfunction "+IN_12") (pintype "input"))
      (node (ref "R101") (pin "2") (pinfunction "2_2") (pintype "passive"))
      (node (ref "R102") (pin "1") (pinfunction "1_1") (pintype "passive"))
      (node (ref "R103") (pin "2") (pinfunction "2_2") (pintype "passive"))
      (node (ref "R106") (pin "2") (pinfunction "2_2") (pintype "passive"))
    )
    (net (code "80") (name "Net-(IC2D-OUT)") (class "Default")
      (node (ref "IC2") (pin "14") (pinfunction "OUT_14") (pintype "output"))
      (node (ref "R102") (pin "2") (pinfunction "2_2") (pintype "passive"))
      (node (ref "R104") (pin "1") (pinfunction "1_1") (pintype "passive"))
    )
    (net (code "81") (name "Net-(IC3A--IN)") (class "Default")
      (node (ref "IC3") (pin "2") (pinfunction "-IN_2") (pintype "input"))
      (node (ref "R401") (pin "1") (pinfunction "1_1") (pintype "passive"))
      (node (ref "R402") (pin "1") (pinfunction "1_1") (pintype "passive"))
      (node (ref "R403") (pin "1") (pinfunction "1_1") (pintype "passive"))
    )
    (net (code "82") (name "Net-(IC3A-OUT)") (class "Default")
      (node (ref "IC3") (pin "1") (pinfunction "OUT_1") (pintype "output"))
      (node (ref "R402") (pin "2") (pinfunction "2_2") (pintype "passive"))
      (node (ref "R404") (pin "1") (pinfunction "1_1") (pintype "passive"))
    )
    (net (code "83") (name "Net-(IC3B--IN)") (class "Default")
      (node (ref "IC3") (pin "6") (pinfunction "-IN_6") (pintype "input"))
      (node (ref "R501") (pin "1") (pinfunction "1_1") (pintype "passive"))
      (node (ref "R502") (pin "1") (pinfunction "1_1") (pintype "passive"))
      (node (ref "R503") (pin "1") (pinfunction "1_1") (pintype "passive"))
    )
    (net (code "84") (name "Net-(IC3B-OUT)") (class "Default")
      (node (ref "IC3") (pin "7") (pinfunction "OUT_7") (pintype "output"))
      (node (ref "R502") (pin "2") (pinfunction "2_2") (pintype "passive"))
      (node (ref "R504") (pin "1") (pinfunction "1_1") (pintype "passive"))
    )
    (net (code "85") (name "Net-(LED1-PadC)") (class "Default")
      (node (ref "LED1") (pin "C") (pinfunction "C_C") (pintype "passive"))
      (node (ref "R2") (pin "2") (pinfunction "2_2") (pintype "passive"))
    )
    (net (code "86") (name "Net-(POT4-Pad2)") (class "Default")
      (node (ref "POT4") (pin "2") (pinfunction "2_2") (pintype "bidirectional"))
      (node (ref "R103") (pin "1") (pinfunction "1_1") (pintype "passive"))
    )
    (net (code "87") (name "Net-(POT5-Pad2)") (class "Default")
      (node (ref "POT5") (pin "2") (pinfunction "2_2") (pintype "bidirectional"))
      (node (ref "R203") (pin "1") (pinfunction "1_1") (pintype "passive"))
    )
    (net (code "88") (name "Net-(POT6-Pad2)") (class "Default")
      (node (ref "POT6") (pin "2") (pinfunction "2_2") (pintype "bidirectional"))
      (node (ref "R303") (pin "1") (pinfunction "1_1") (pintype "passive"))
    )
    (net (code "89") (name "Net-(POT7-Pad2)") (class "Default")
      (node (ref "POT7") (pin "2") (pinfunction "2_2") (pintype "bidirectional"))
      (node (ref "R101") (pin "1") (pinfunction "1_1") (pintype "passive"))
    )
    (net (code "90") (name "Net-(POT8-Pad2)") (class "Default")
      (node (ref "POT8") (pin "2") (pinfunction "2_2") (pintype "bidirectional"))
      (node (ref "R201") (pin "1") (pinfunction "1_1") (pintype "passive"))
    )
    (net (code "91") (name "Net-(POT9-Pad2)") (class "Default")
      (node (ref "POT9") (pin "2") (pinfunction "2_2") (pintype "bidirectional"))
      (node (ref "R301") (pin "1") (pinfunction "1_1") (pintype "passive"))
    )
    (net (code "92") (name "Net-(Q301-B)") (class "Default")
      (node (ref "Q301") (pin "1") (pinfunction "B_1") (pintype "passive"))
      (node (ref "R601") (pin "2") (pinfunction "2_2") (pintype "passive"))
      (node (ref "R602") (pin "1") (pinfunction "1_1") (pintype "passive"))
    )
    (net (code "93") (name "Net-(Q701-B)") (class "Default")
      (node (ref "Q701") (pin "1") (pinfunction "B_1") (pintype "passive"))
      (node (ref "R701") (pin "2") (pinfunction "2_2") (pintype "passive"))
    )
    (net (code "94") (name "Net-(Q701-C)") (class "Default")
      (node (ref "Q701") (pin "3") (pinfunction "C_3") (pintype "passive"))
      (node (ref "R702") (pin "2") (pinfunction "2_2") (pintype "passive"))
      (node (ref "R703") (pin "1") (pinfunction "1_1") (pintype "passive"))
    )
    (net (code "95") (name "Net-(Q801-B)") (class "Default")
      (node (ref "Q801") (pin "1") (pinfunction "B_1") (pintype "passive"))
      (node (ref "R801") (pin "2") (pinfunction "2_2") (pintype "passive"))
    )
    (net (code "96") (name "Net-(Q801-C)") (class "Default")
      (node (ref "Q801") (pin "3") (pinfunction "C_3") (pintype "passive"))
      (node (ref "R802") (pin "2") (pinfunction "2_2") (pintype "passive"))
      (node (ref "R803") (pin "1") (pinfunction "1_1") (pintype "passive"))
    )
    (net (code "97") (name "Net-(Q901-B)") (class "Default")
      (node (ref "Q901") (pin "1") (pinfunction "B_1") (pintype "passive"))
      (node (ref "R901") (pin "2") (pinfunction "2_2") (pintype "passive"))
      (node (ref "R902") (pin "1") (pinfunction "1_1") (pintype "passive"))
    )
    (net (code "98") (name "unconnected-(DAC0-PadSW)") (class "Default")
      (node (ref "DAC0") (pin "SW") (pinfunction "SW_SW") (pintype "passive"))
    )
    (net (code "99") (name "unconnected-(DAC1-PadSW)") (class "Default")
      (node (ref "DAC1") (pin "SW") (pinfunction "SW_SW") (pintype "passive"))
    )
    (net (code "100") (name "unconnected-(DGO0-PadSW)") (class "Default")
      (node (ref "DGO0") (pin "SW") (pinfunction "SW_SW") (pintype "passive"))
    )
    (net (code "101") (name "unconnected-(DGO1-PadSW)") (class "Default")
      (node (ref "DGO1") (pin "SW") (pinfunction "SW_SW") (pintype "passive"))
    )
    (net (code "102") (name "unconnected-(U$2-Pad13)") (class "Default")
      (node (ref "U$2") (pin "13") (pinfunction "13_13") (pintype "passive"))
    )
    (net (code "103") (name "unconnected-(U$2-Pad14)") (class "Default")
      (node (ref "U$2") (pin "14") (pinfunction "14_14") (pintype "passive"))
    )
    (net (code "104") (name "unconnected-(U$2-Pad15)") (class "Default")
      (node (ref "U$2") (pin "15") (pinfunction "15_15") (pintype "passive"))
    )
    (net (code "105") (name "unconnected-(U$2-Pad16)") (class "Default")
      (node (ref "U$2") (pin "16") (pinfunction "16_16") (pintype "passive"))
    )
    (net (code "106") (name "unconnected-(U1H-PD0{slash}OSC<=-Pad5)") (class "Default")
      (node (ref "U1") (pin "5") (pinfunction "PD0/OSC<=_5") (pintype "bidirectional"))
    )
    (net (code "107") (name "unconnected-(U1H-PD1{slash}OSC=>-Pad6)") (class "Default")
      (node (ref "U1") (pin "6") (pinfunction "PD1/OSC=>_6") (pintype "bidirectional"))
    )
  )
)
